# Sunfish_ECU_Power_RevA.net
KiCad netlist of a schematic drawn in Altium Designer
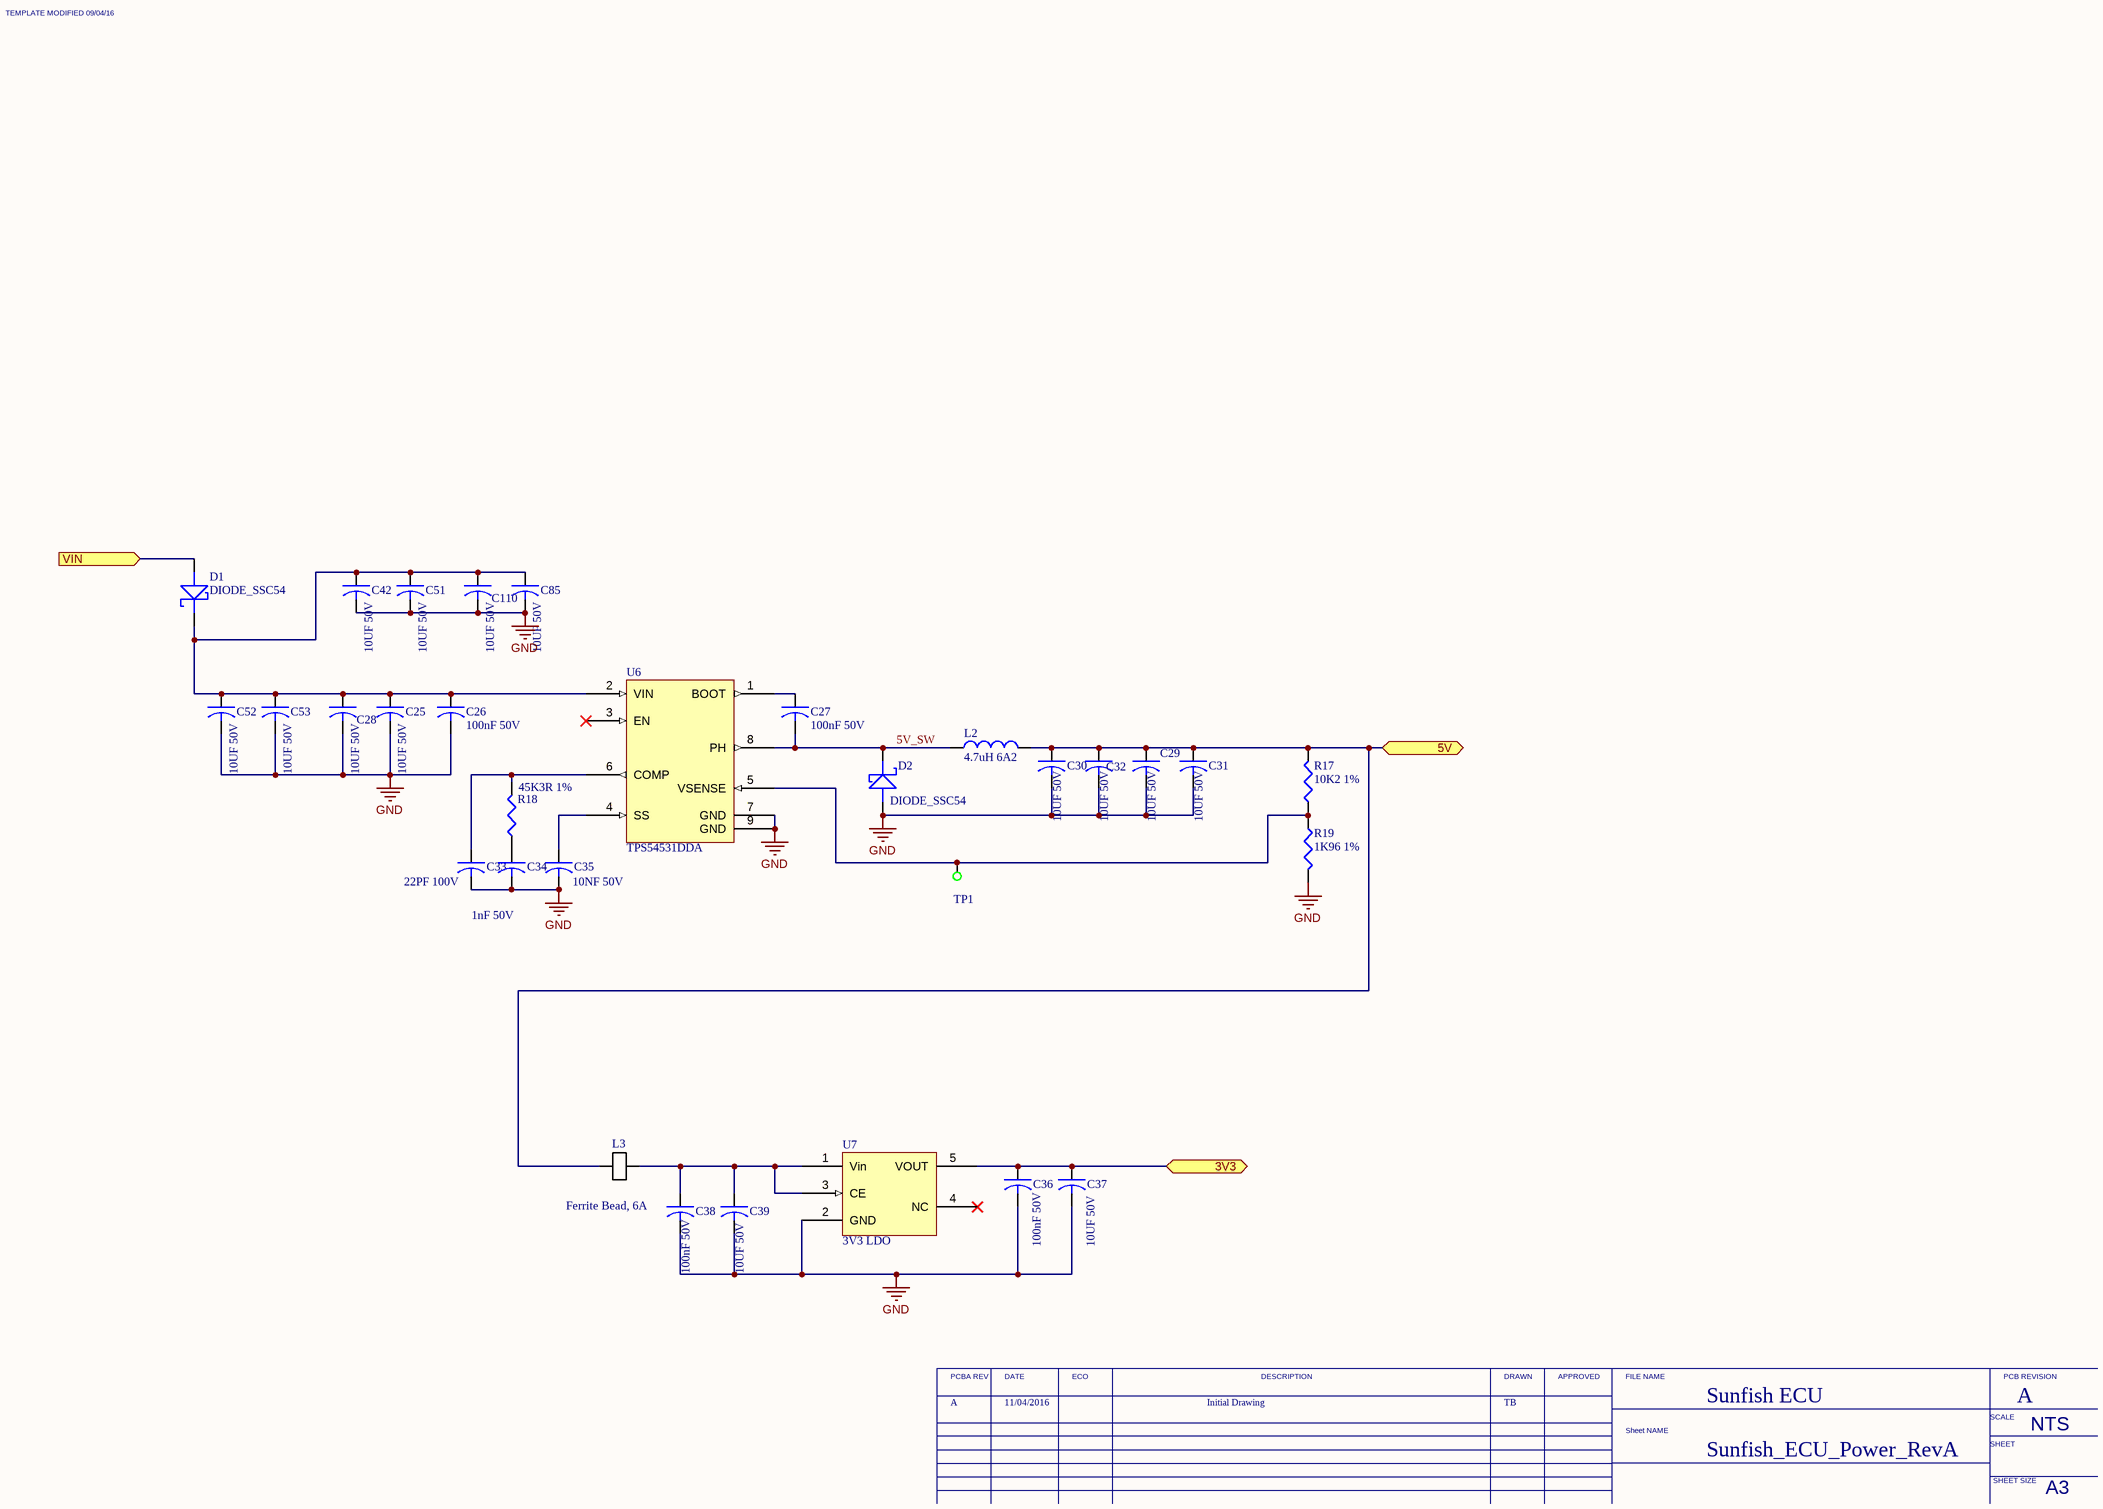
[diagram p0: Sunfish_ECU_Power_RevA.SchDoc]

(export (version "E")
  (design (tool "Eeschema 10.0.6"))
  (components
    (comp (ref "C25")
      (value "10UF 50V")
      (footprint "1206")
      (description "CAP CER 10UF 50V 10% X5R 1206")
      (fields (field (name "MANUFACTURER") "Murata"))
      (libsource (lib "Regulators") (part "CAP_10UF_50V_10%_1206"))
    )
    (comp (ref "C26")
      (value "100nF 50V")
      (footprint "0603")
      (description "CAP CER 100nF 50V 10% X7R 0603")
      (fields (field (name "MANUFACTURER") "Murata"))
      (libsource (lib "Caps") (part "CAP_100NF_50V_10%_0603"))
    )
    (comp (ref "C27")
      (value "100nF 50V")
      (footprint "0603")
      (description "CAP CER 100nF 50V 10% X7R 0603")
      (fields (field (name "MANUFACTURER") "Murata"))
      (libsource (lib "Caps") (part "CAP_100NF_50V_10%_0603"))
    )
    (comp (ref "C28")
      (value "10UF 50V")
      (footprint "1206")
      (description "CAP CER 10UF 50V 10% X5R 1206")
      (fields (field (name "MANUFACTURER") "Murata"))
      (libsource (lib "Regulators") (part "CAP_10UF_50V_10%_1206"))
    )
    (comp (ref "C29")
      (value "10UF 50V")
      (footprint "1206")
      (description "CAP CER 10UF 50V 10% X5R 1206")
      (fields (field (name "MANUFACTURER") "Murata"))
      (libsource (lib "ThrusterControl") (part "CAP_10UF_50V_10%_1206"))
    )
    (comp (ref "C30")
      (value "10UF 50V")
      (footprint "1206")
      (description "CAP CER 10UF 50V 10% X5R 1206")
      (fields (field (name "MANUFACTURER") "Murata"))
      (libsource (lib "ThrusterControl") (part "CAP_10UF_50V_10%_1206"))
    )
    (comp (ref "C31")
      (value "10UF 50V")
      (footprint "1206")
      (description "CAP CER 10UF 50V 10% X5R 1206")
      (fields (field (name "MANUFACTURER") "Murata"))
      (libsource (lib "ThrusterControl") (part "CAP_10UF_50V_10%_1206"))
    )
    (comp (ref "C32")
      (value "10UF 50V")
      (footprint "1206")
      (description "CAP CER 10UF 50V 10% X5R 1206")
      (fields (field (name "MANUFACTURER") "Murata"))
      (libsource (lib "ThrusterControl") (part "CAP_10UF_50V_10%_1206"))
    )
    (comp (ref "C33")
      (value "22PF 100V")
      (footprint "0603")
      (description "CAP CER 22PF 100V 5% NP0 0603")
      (fields (field (name "MANUFACTURER") "Murata"))
      (libsource (lib "Caps") (part "CAP_22PF_100V_5%_0603"))
    )
    (comp (ref "C34")
      (value "1nF 50V")
      (footprint "0603")
      (description "CAP CER 1nF 50V 10% X7R 0603")
      (fields (field (name "MANUFACTURER") "Murata"))
      (libsource (lib "Caps") (part "CAP_1NF_50V_10%_0603"))
    )
    (comp (ref "C35")
      (value "10NF 50V")
      (footprint "0603")
      (description "CAP CER 10NF 50V 10% X7R 0603")
      (fields (field (name "MANUFACTURER") "Murata"))
      (libsource (lib "Regulators") (part "CAP_10NF_50V_10%_0603"))
    )
    (comp (ref "C36")
      (value "100nF 50V")
      (footprint "0603")
      (description "CAP CER 100nF 50V 10% X7R 0603")
      (fields (field (name "MANUFACTURER") "Murata"))
      (libsource (lib "Caps") (part "CAP_100NF_50V_10%_0603"))
    )
    (comp (ref "C37")
      (value "10UF 50V")
      (footprint "1206")
      (description "CAP CER 10UF 50V 10% X5R 1206")
      (fields (field (name "MANUFACTURER") "Murata"))
      (libsource (lib "ThrusterControl") (part "CAP_10UF_50V_10%_1206"))
    )
    (comp (ref "C38")
      (value "100nF 50V")
      (footprint "0603")
      (description "CAP CER 100nF 50V 10% X7R 0603")
      (fields (field (name "MANUFACTURER") "Murata"))
      (libsource (lib "Caps") (part "CAP_100NF_50V_10%_0603"))
    )
    (comp (ref "C39")
      (value "10UF 50V")
      (footprint "1206")
      (description "CAP CER 10UF 50V 10% X5R 1206")
      (fields (field (name "MANUFACTURER") "Murata"))
      (libsource (lib "ThrusterControl") (part "CAP_10UF_50V_10%_1206"))
    )
    (comp (ref "C42")
      (value "10UF 50V")
      (footprint "1206")
      (description "CAP CER 10UF 50V 10% X5R 1206")
      (fields (field (name "MANUFACTURER") "Murata"))
      (libsource (lib "Regulators") (part "CAP_10UF_50V_10%_1206"))
    )
    (comp (ref "C51")
      (value "10UF 50V")
      (footprint "1206")
      (description "CAP CER 10UF 50V 10% X5R 1206")
      (fields (field (name "MANUFACTURER") "Murata"))
      (libsource (lib "Regulators") (part "CAP_10UF_50V_10%_1206"))
    )
    (comp (ref "C52")
      (value "10UF 50V")
      (footprint "1206")
      (description "CAP CER 10UF 50V 10% X5R 1206")
      (fields (field (name "MANUFACTURER") "Murata"))
      (libsource (lib "Regulators") (part "CAP_10UF_50V_10%_1206"))
    )
    (comp (ref "C53")
      (value "10UF 50V")
      (footprint "1206")
      (description "CAP CER 10UF 50V 10% X5R 1206")
      (fields (field (name "MANUFACTURER") "Murata"))
      (libsource (lib "Regulators") (part "CAP_10UF_50V_10%_1206"))
    )
    (comp (ref "C85")
      (value "10UF 50V")
      (footprint "1206")
      (description "CAP CER 10UF 50V 10% X5R 1206")
      (fields (field (name "MANUFACTURER") "Murata"))
      (libsource (lib "Regulators") (part "CAP_10UF_50V_10%_1206"))
    )
    (comp (ref "C110")
      (value "10UF 50V")
      (footprint "1206")
      (description "CAP CER 10UF 50V 10% X5R 1206")
      (fields (field (name "MANUFACTURER") "Murata"))
      (libsource (lib "Regulators") (part "CAP_10UF_50V_10%_1206"))
    )
    (comp (ref "D1")
      (value "DIODE_SSC54")
      (footprint "DO-214AB")
      (description "Schottky Diode, 5A, 40V SSC54, DO214AB")
      (fields (field (name "MANUFACTURER") "Vishay"))
      (libsource (lib "Regulators") (part "DIODE_SSC54"))
    )
    (comp (ref "D2")
      (value "DIODE_SSC54")
      (footprint "DO-214AB")
      (description "Schottky Diode, 5A, 40V SSC54, DO214AB")
      (fields (field (name "MANUFACTURER") "Vishay"))
      (libsource (lib "Regulators") (part "DIODE_SSC54"))
    )
    (comp (ref "L2")
      (value "4.7uH 6A2")
      (footprint "Wurth744771156")
      (description "FIXED IND 4.7UH 6.2A 34 MOHM")
      (fields (field (name "MANUFACTURER") "Wurth Electronics Inc"))
      (libsource (lib "Inductors") (part "IND_4.7uH_6A2"))
    )
    (comp (ref "L3")
      (value "Ferrite Bead, 6A")
      (footprint "1806")
      (fields (field (name "MANUFACTURER") "MURATA"))
      (libsource (lib "Inductors") (part "IND_FERRITE_ BLM41PG600SN1L"))
    )
    (comp (ref "R17")
      (value "10K2 1%")
      (footprint "0603")
      (description "Resistor, 10K2, 1%, 0603")
      (fields (field (name "MANUFACTURER") "Yageo"))
      (libsource (lib "Resistors") (part "RES_10K2_1%_0603"))
    )
    (comp (ref "R18")
      (value "45K3R 1%")
      (footprint "0603")
      (description "Resistor, 45K3, 1%, 0603")
      (fields (field (name "MANUFACTURER") "Bourns Inc"))
      (libsource (lib "Resistors") (part "RES_45K3_1%_0603"))
    )
    (comp (ref "R19")
      (value "1K96 1%")
      (footprint "0603")
      (description "Resistor, 1K96, 1%, 0603")
      (fields (field (name "MANUFACTURER") "Yageo"))
      (libsource (lib "Resistors") (part "RES_1K96_1%_0603"))
    )
    (comp (ref "TP1")
      (value "Test Point")
      (footprint "TP_SMT")
      (description "Probe compatible test point")
      (libsource (lib "Hardware") (part "MISC_TP_SMT"))
    )
    (comp (ref "U6")
      (value "TPS54531DDA")
      (footprint "PSOP-8")
      (description "SMPS")
      (fields (field (name "MANUFACTURER") "TI"))
      (libsource (lib "IC") (part "IC_SMPS_TPS54531"))
    )
    (comp (ref "U7")
      (value "3V3 LDO")
      (footprint "SOT-25-A")
      (description "IC REG LDO 3.3V 0.7A SOT25")
      (fields (field (name "MANUFACTURER") "Torex Semiconductor Ltd"))
      (libsource (lib "ThrusterControl") (part "IC_XC6210B332MR-G"))
    )
  )
  (nets
    (net (code "1") (name "/3V3") (class "Default")
      (node (ref "C36") (pin "1") (pinfunction "1_1") (pintype "passive"))
      (node (ref "C37") (pin "1") (pinfunction "1_1") (pintype "passive"))
      (node (ref "U7") (pin "5") (pinfunction "VOUT_5") (pintype "power_in"))
    )
    (net (code "2") (name "/5V") (class "Default")
      (node (ref "C29") (pin "1") (pinfunction "1_1") (pintype "passive"))
      (node (ref "C30") (pin "1") (pinfunction "1_1") (pintype "passive"))
      (node (ref "C31") (pin "1") (pinfunction "1_1") (pintype "passive"))
      (node (ref "C32") (pin "1") (pinfunction "1_1") (pintype "passive"))
      (node (ref "L2") (pin "2") (pinfunction "2_2") (pintype "passive"))
      (node (ref "L3") (pin "1") (pinfunction "1_1") (pintype "passive"))
      (node (ref "R17") (pin "2") (pintype "passive"))
    )
    (net (code "3") (name "/5V_SW") (class "Default")
      (node (ref "C27") (pin "2") (pinfunction "2_2") (pintype "passive"))
      (node (ref "D2") (pin "K") (pinfunction "K_K") (pintype "passive"))
      (node (ref "L2") (pin "1") (pinfunction "1_1") (pintype "passive"))
      (node (ref "U6") (pin "8") (pinfunction "PH_8") (pintype "output"))
    )
    (net (code "4") (name "/VIN") (class "Default")
      (node (ref "D1") (pin "A") (pinfunction "A_A") (pintype "passive"))
    )
    (net (code "5") (name "GND") (class "Default")
      (node (ref "C110") (pin "2") (pinfunction "2_2") (pintype "passive"))
      (node (ref "C25") (pin "2") (pinfunction "2_2") (pintype "passive"))
      (node (ref "C26") (pin "2") (pinfunction "2_2") (pintype "passive"))
      (node (ref "C28") (pin "2") (pinfunction "2_2") (pintype "passive"))
      (node (ref "C29") (pin "2") (pinfunction "2_2") (pintype "passive"))
      (node (ref "C30") (pin "2") (pinfunction "2_2") (pintype "passive"))
      (node (ref "C31") (pin "2") (pinfunction "2_2") (pintype "passive"))
      (node (ref "C32") (pin "2") (pinfunction "2_2") (pintype "passive"))
      (node (ref "C33") (pin "2") (pinfunction "2_2") (pintype "passive"))
      (node (ref "C34") (pin "2") (pinfunction "2_2") (pintype "passive"))
      (node (ref "C35") (pin "2") (pinfunction "2_2") (pintype "passive"))
      (node (ref "C36") (pin "2") (pinfunction "2_2") (pintype "passive"))
      (node (ref "C37") (pin "2") (pinfunction "2_2") (pintype "passive"))
      (node (ref "C38") (pin "2") (pinfunction "2_2") (pintype "passive"))
      (node (ref "C39") (pin "2") (pinfunction "2_2") (pintype "passive"))
      (node (ref "C42") (pin "2") (pinfunction "2_2") (pintype "passive"))
      (node (ref "C51") (pin "2") (pinfunction "2_2") (pintype "passive"))
      (node (ref "C52") (pin "2") (pinfunction "2_2") (pintype "passive"))
      (node (ref "C53") (pin "2") (pinfunction "2_2") (pintype "passive"))
      (node (ref "C85") (pin "2") (pinfunction "2_2") (pintype "passive"))
      (node (ref "D2") (pin "A") (pinfunction "A_A") (pintype "passive"))
      (node (ref "R19") (pin "2") (pintype "passive"))
      (node (ref "U6") (pin "7") (pinfunction "GND_7") (pintype "power_in"))
      (node (ref "U6") (pin "9") (pinfunction "GND_9") (pintype "power_in"))
      (node (ref "U7") (pin "2") (pinfunction "GND_2") (pintype "power_in"))
    )
    (net (code "6") (name "Net-(C34-Pad1)") (class "Default")
      (node (ref "C34") (pin "1") (pinfunction "1_1") (pintype "passive"))
      (node (ref "R18") (pin "1") (pintype "passive"))
    )
    (net (code "7") (name "Net-(U6-BOOT)") (class "Default")
      (node (ref "C27") (pin "1") (pinfunction "1_1") (pintype "passive"))
      (node (ref "U6") (pin "1") (pinfunction "BOOT_1") (pintype "output"))
    )
    (net (code "8") (name "Net-(U6-COMP)") (class "Default")
      (node (ref "C33") (pin "1") (pinfunction "1_1") (pintype "passive"))
      (node (ref "R18") (pin "2") (pintype "passive"))
      (node (ref "U6") (pin "6") (pinfunction "COMP_6") (pintype "output"))
    )
    (net (code "9") (name "Net-(U6-SS)") (class "Default")
      (node (ref "C35") (pin "1") (pinfunction "1_1") (pintype "passive"))
      (node (ref "U6") (pin "4") (pinfunction "SS_4") (pintype "input"))
    )
    (net (code "10") (name "Net-(U6-VIN)") (class "Default")
      (node (ref "C110") (pin "1") (pinfunction "1_1") (pintype "passive"))
      (node (ref "C25") (pin "1") (pinfunction "1_1") (pintype "passive"))
      (node (ref "C26") (pin "1") (pinfunction "1_1") (pintype "passive"))
      (node (ref "C28") (pin "1") (pinfunction "1_1") (pintype "passive"))
      (node (ref "C42") (pin "1") (pinfunction "1_1") (pintype "passive"))
      (node (ref "C51") (pin "1") (pinfunction "1_1") (pintype "passive"))
      (node (ref "C52") (pin "1") (pinfunction "1_1") (pintype "passive"))
      (node (ref "C53") (pin "1") (pinfunction "1_1") (pintype "passive"))
      (node (ref "C85") (pin "1") (pinfunction "1_1") (pintype "passive"))
      (node (ref "D1") (pin "K") (pinfunction "K_K") (pintype "passive"))
      (node (ref "U6") (pin "2") (pinfunction "VIN_2") (pintype "input"))
    )
    (net (code "11") (name "Net-(U6-VSENSE)") (class "Default")
      (node (ref "R17") (pin "1") (pintype "passive"))
      (node (ref "R19") (pin "1") (pintype "passive"))
      (node (ref "TP1") (pin "1") (pinfunction "1_1") (pintype "passive"))
      (node (ref "U6") (pin "5") (pinfunction "VSENSE_5") (pintype "input"))
    )
    (net (code "12") (name "Net-(U7-CE)") (class "Default")
      (node (ref "C38") (pin "1") (pinfunction "1_1") (pintype "passive"))
      (node (ref "C39") (pin "1") (pinfunction "1_1") (pintype "passive"))
      (node (ref "L3") (pin "2") (pinfunction "2_2") (pintype "passive"))
      (node (ref "U7") (pin "1") (pinfunction "Vin_1") (pintype "power_in"))
      (node (ref "U7") (pin "3") (pinfunction "CE_3") (pintype "input"))
    )
    (net (code "13") (name "unconnected-(U6-EN-Pad3)") (class "Default")
      (node (ref "U6") (pin "3") (pinfunction "EN_3") (pintype "input+no_connect"))
    )
    (net (code "14") (name "unconnected-(U7-NC-Pad4)") (class "Default")
      (node (ref "U7") (pin "4") (pinfunction "NC_4") (pintype "tri_state+no_connect"))
    )
  )
)
